# stm32f4stamp-20131027.net
KiCad netlist of a schematic drawn in EAGLE
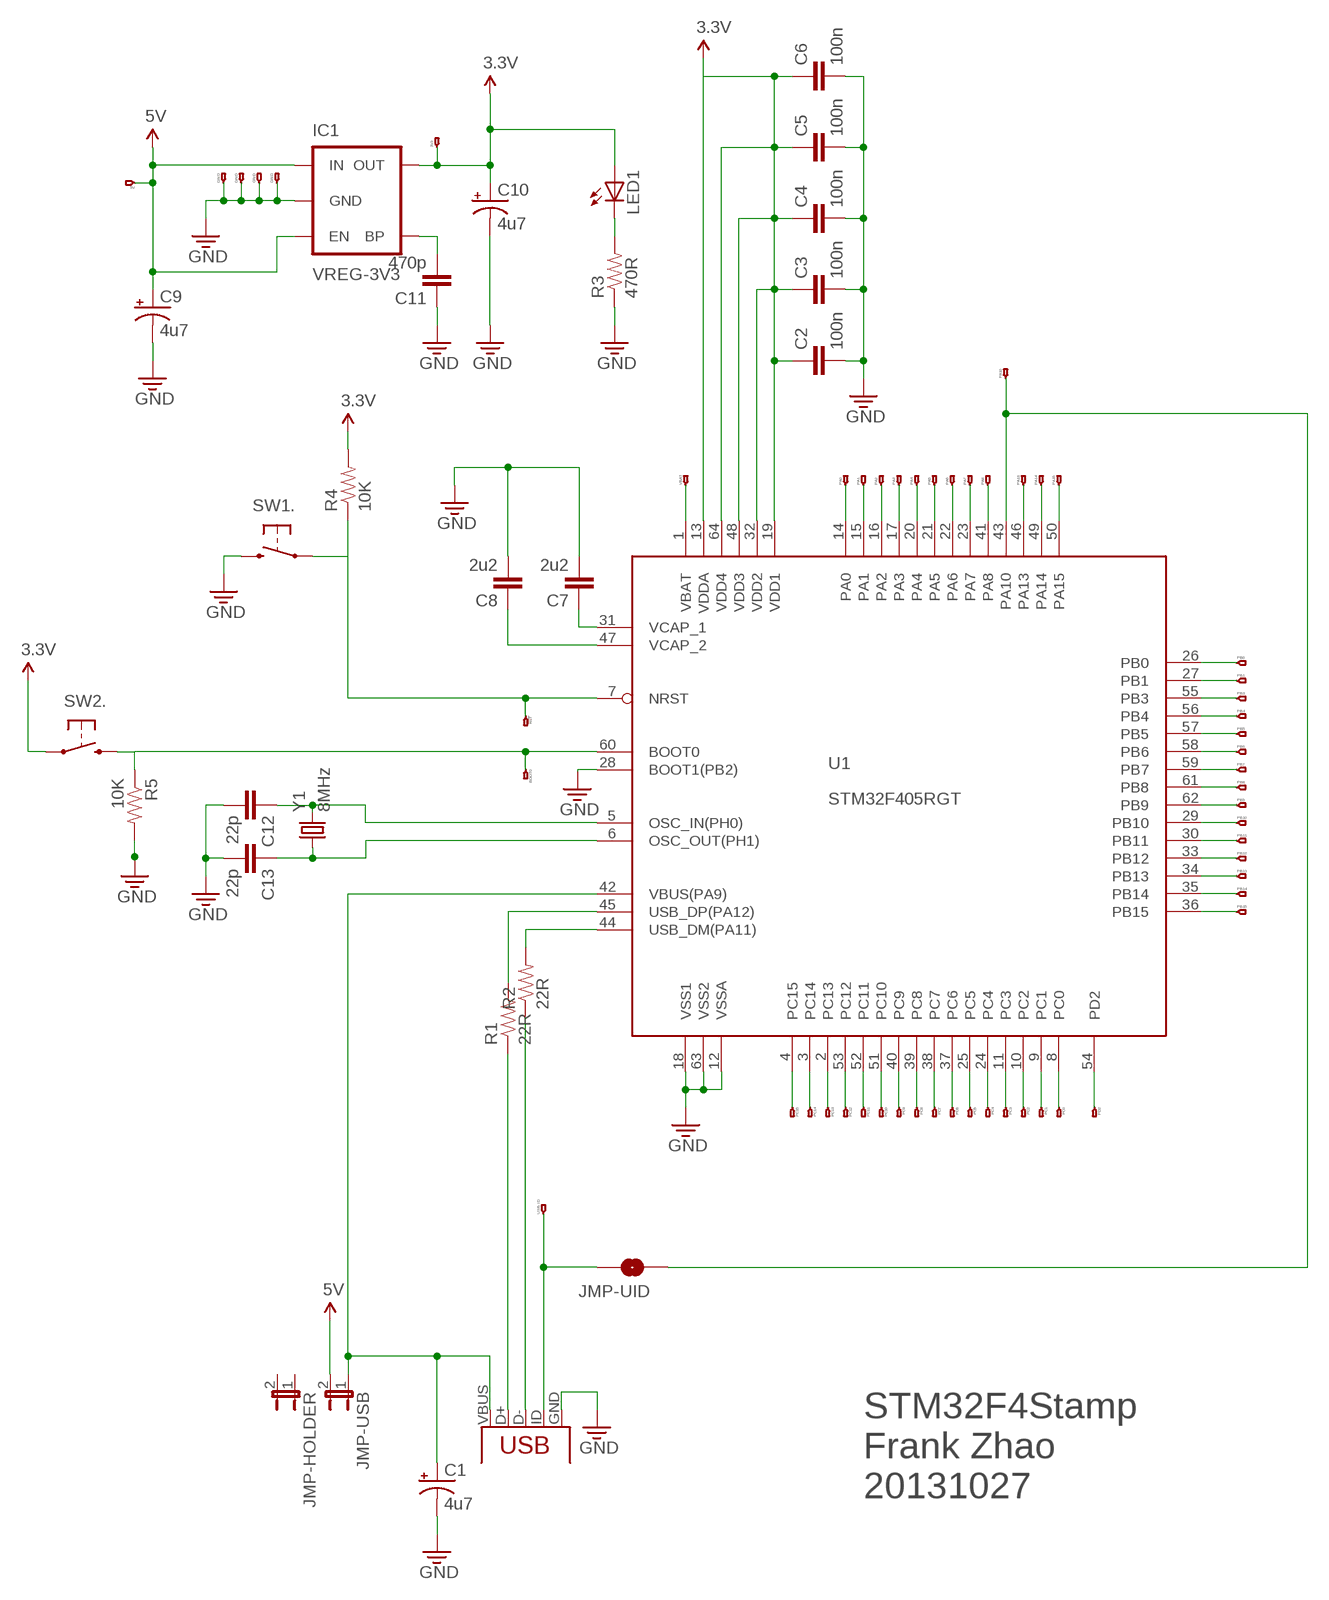
[diagram p0: schematic, sheet 1]

(export (version "E")
  (design (tool "Eeschema 10.0.6"))
  (components
    (comp (ref "C1")
      (value "4u7")
      (footprint "eagle-import:EIA3216-KIT")
      (libsource (lib "eagle-import") (part "CAP_POL1206-KIT"))
    )
    (comp (ref "C2")
      (value "100n")
      (footprint "eagle-import:0603-CAP")
      (libsource (lib "eagle-import") (part "CAP0603-CAP"))
    )
    (comp (ref "C3")
      (value "100n")
      (footprint "eagle-import:0603-CAP")
      (libsource (lib "eagle-import") (part "CAP0603-CAP"))
    )
    (comp (ref "C4")
      (value "100n")
      (footprint "eagle-import:0603-CAP")
      (libsource (lib "eagle-import") (part "CAP0603-CAP"))
    )
    (comp (ref "C5")
      (value "100n")
      (footprint "eagle-import:0603-CAP")
      (libsource (lib "eagle-import") (part "CAP0603-CAP"))
    )
    (comp (ref "C6")
      (value "100n")
      (footprint "eagle-import:0603-CAP")
      (libsource (lib "eagle-import") (part "CAP0603-CAP"))
    )
    (comp (ref "C7")
      (value "2u2")
      (footprint "eagle-import:0603-CAP")
      (libsource (lib "eagle-import") (part "CAP0603-CAP"))
    )
    (comp (ref "C8")
      (value "2u2")
      (footprint "eagle-import:0603-CAP")
      (libsource (lib "eagle-import") (part "CAP0603-CAP"))
    )
    (comp (ref "C9")
      (value "4u7")
      (footprint "eagle-import:EIA3216-KIT")
      (libsource (lib "eagle-import") (part "CAP_POL1206-KIT"))
    )
    (comp (ref "C10")
      (value "4u7")
      (footprint "eagle-import:EIA3216-KIT")
      (libsource (lib "eagle-import") (part "CAP_POL1206-KIT"))
    )
    (comp (ref "C11")
      (value "470p")
      (footprint "eagle-import:0603-CAP")
      (libsource (lib "eagle-import") (part "CAP0603-CAP"))
    )
    (comp (ref "C12")
      (value "22p")
      (footprint "eagle-import:0603-CAP")
      (libsource (lib "eagle-import") (part "CAP0603-CAP"))
    )
    (comp (ref "C13")
      (value "22p")
      (footprint "eagle-import:0603-CAP")
      (libsource (lib "eagle-import") (part "CAP0603-CAP"))
    )
    (comp (ref "IC1")
      (value "VREG-3V3")
      (footprint "eagle-import:SOT23-5")
      (libsource (lib "eagle-import") (part "V_REG_LDOSMD"))
    )
    (comp (ref "JMP-HOLDER")
      (value "JUMPER-2-PTH-2MM")
      (footprint "eagle-import:1X02_2MM_TH")
      (libsource (lib "eagle-import") (part "JUMPER-2-PTH-2MM"))
    )
    (comp (ref "JMP-UID")
      (value "SOLDERJUMPERNC")
      (footprint "eagle-import:SJ_2S")
      (libsource (lib "eagle-import") (part "SOLDERJUMPERNC"))
    )
    (comp (ref "JMP-USB")
      (value "JUMPER-2-PTH-2MM")
      (footprint "eagle-import:1X02_2MM_TH")
      (libsource (lib "eagle-import") (part "JUMPER-2-PTH-2MM"))
    )
    (comp (ref "JP2")
      (value "5V")
      (footprint "eagle-import:1X1-HEADER-HOLE")
      (libsource (lib "eagle-import") (part "HEADERHOLE-HEADERHOLE"))
    )
    (comp (ref "JP3")
      (value "GND")
      (footprint "eagle-import:1X1-HEADER-HOLE")
      (libsource (lib "eagle-import") (part "HEADERHOLE-HEADERHOLE"))
    )
    (comp (ref "JP4")
      (value "3V3")
      (footprint "eagle-import:1X1-HEADER-HOLE")
      (libsource (lib "eagle-import") (part "HEADERHOLE-HEADERHOLE"))
    )
    (comp (ref "JP5")
      (value "GND")
      (footprint "eagle-import:1X1-HEADER-HOLE")
      (libsource (lib "eagle-import") (part "HEADERHOLE-HEADERHOLE"))
    )
    (comp (ref "JP6")
      (value "GND")
      (footprint "eagle-import:1X1-HEADER-HOLE")
      (libsource (lib "eagle-import") (part "HEADERHOLE-HEADERHOLE"))
    )
    (comp (ref "JP7")
      (value "GND")
      (footprint "eagle-import:1X1-HEADER-HOLE")
      (libsource (lib "eagle-import") (part "HEADERHOLE-HEADERHOLE"))
    )
    (comp (ref "JP8")
      (value "PB8")
      (footprint "eagle-import:1X1-HEADER-HOLE")
      (libsource (lib "eagle-import") (part "HEADERHOLE-HEADERHOLE"))
    )
    (comp (ref "JP9")
      (value "PA10")
      (footprint "eagle-import:1X1-HEADER-HOLE")
      (libsource (lib "eagle-import") (part "HEADERHOLE-HEADERHOLE"))
    )
    (comp (ref "JP10")
      (value "PA8")
      (footprint "eagle-import:1X1-HEADER-HOLE")
      (libsource (lib "eagle-import") (part "HEADERHOLE-HEADERHOLE"))
    )
    (comp (ref "JP11")
      (value "PA13")
      (footprint "eagle-import:1X1-HEADER-HOLE")
      (libsource (lib "eagle-import") (part "HEADERHOLE-HEADERHOLE"))
    )
    (comp (ref "JP12")
      (value "PC9")
      (footprint "eagle-import:1X1-HEADER-HOLE")
      (libsource (lib "eagle-import") (part "HEADERHOLE-HEADERHOLE"))
    )
    (comp (ref "JP13")
      (value "PC15")
      (footprint "eagle-import:1X1-HEADER-HOLE")
      (libsource (lib "eagle-import") (part "HEADERHOLE-HEADERHOLE"))
    )
    (comp (ref "JP14")
      (value "PC14")
      (footprint "eagle-import:1X1-HEADER-HOLE")
      (libsource (lib "eagle-import") (part "HEADERHOLE-HEADERHOLE"))
    )
    (comp (ref "JP15")
      (value "PC13")
      (footprint "eagle-import:1X1-HEADER-HOLE")
      (libsource (lib "eagle-import") (part "HEADERHOLE-HEADERHOLE"))
    )
    (comp (ref "JP16")
      (value "PC12")
      (footprint "eagle-import:1X1-HEADER-HOLE")
      (libsource (lib "eagle-import") (part "HEADERHOLE-HEADERHOLE"))
    )
    (comp (ref "JP17")
      (value "PC11")
      (footprint "eagle-import:1X1-HEADER-HOLE")
      (libsource (lib "eagle-import") (part "HEADERHOLE-HEADERHOLE"))
    )
    (comp (ref "JP18")
      (value "PC10")
      (footprint "eagle-import:1X1-HEADER-HOLE")
      (libsource (lib "eagle-import") (part "HEADERHOLE-HEADERHOLE"))
    )
    (comp (ref "JP19")
      (value "PC8")
      (footprint "eagle-import:1X1-HEADER-HOLE")
      (libsource (lib "eagle-import") (part "HEADERHOLE-HEADERHOLE"))
    )
    (comp (ref "JP20")
      (value "PC7")
      (footprint "eagle-import:1X1-HEADER-HOLE")
      (libsource (lib "eagle-import") (part "HEADERHOLE-HEADERHOLE"))
    )
    (comp (ref "JP21")
      (value "PC6")
      (footprint "eagle-import:1X1-HEADER-HOLE")
      (libsource (lib "eagle-import") (part "HEADERHOLE-HEADERHOLE"))
    )
    (comp (ref "JP22")
      (value "PC5")
      (footprint "eagle-import:1X1-HEADER-HOLE")
      (libsource (lib "eagle-import") (part "HEADERHOLE-HEADERHOLE"))
    )
    (comp (ref "JP23")
      (value "PC4")
      (footprint "eagle-import:1X1-HEADER-HOLE")
      (libsource (lib "eagle-import") (part "HEADERHOLE-HEADERHOLE"))
    )
    (comp (ref "JP24")
      (value "PC3")
      (footprint "eagle-import:1X1-HEADER-HOLE")
      (libsource (lib "eagle-import") (part "HEADERHOLE-HEADERHOLE"))
    )
    (comp (ref "JP25")
      (value "PC2")
      (footprint "eagle-import:1X1-HEADER-HOLE")
      (libsource (lib "eagle-import") (part "HEADERHOLE-HEADERHOLE"))
    )
    (comp (ref "JP26")
      (value "PC1")
      (footprint "eagle-import:1X1-HEADER-HOLE")
      (libsource (lib "eagle-import") (part "HEADERHOLE-HEADERHOLE"))
    )
    (comp (ref "JP27")
      (value "PC0")
      (footprint "eagle-import:1X1-HEADER-HOLE")
      (libsource (lib "eagle-import") (part "HEADERHOLE-HEADERHOLE"))
    )
    (comp (ref "JP28")
      (value "PD2")
      (footprint "eagle-import:1X1-HEADER-HOLE")
      (libsource (lib "eagle-import") (part "HEADERHOLE-HEADERHOLE"))
    )
    (comp (ref "JP29")
      (value "PA0")
      (footprint "eagle-import:1X1-HEADER-HOLE")
      (libsource (lib "eagle-import") (part "HEADERHOLE-HEADERHOLE"))
    )
    (comp (ref "JP30")
      (value "PA1")
      (footprint "eagle-import:1X1-HEADER-HOLE")
      (libsource (lib "eagle-import") (part "HEADERHOLE-HEADERHOLE"))
    )
    (comp (ref "JP31")
      (value "PA2")
      (footprint "eagle-import:1X1-HEADER-HOLE")
      (libsource (lib "eagle-import") (part "HEADERHOLE-HEADERHOLE"))
    )
    (comp (ref "JP32")
      (value "PA3")
      (footprint "eagle-import:1X1-HEADER-HOLE")
      (libsource (lib "eagle-import") (part "HEADERHOLE-HEADERHOLE"))
    )
    (comp (ref "JP33")
      (value "PA4")
      (footprint "eagle-import:1X1-HEADER-HOLE")
      (libsource (lib "eagle-import") (part "HEADERHOLE-HEADERHOLE"))
    )
    (comp (ref "JP34")
      (value "PA5")
      (footprint "eagle-import:1X1-HEADER-HOLE")
      (libsource (lib "eagle-import") (part "HEADERHOLE-HEADERHOLE"))
    )
    (comp (ref "JP35")
      (value "PA6")
      (footprint "eagle-import:1X1-HEADER-HOLE")
      (libsource (lib "eagle-import") (part "HEADERHOLE-HEADERHOLE"))
    )
    (comp (ref "JP36")
      (value "PA7")
      (footprint "eagle-import:1X1-HEADER-HOLE")
      (libsource (lib "eagle-import") (part "HEADERHOLE-HEADERHOLE"))
    )
    (comp (ref "JP37")
      (value "PA14")
      (footprint "eagle-import:1X1-HEADER-HOLE")
      (libsource (lib "eagle-import") (part "HEADERHOLE-HEADERHOLE"))
    )
    (comp (ref "JP38")
      (value "PA15")
      (footprint "eagle-import:1X1-HEADER-HOLE")
      (libsource (lib "eagle-import") (part "HEADERHOLE-HEADERHOLE"))
    )
    (comp (ref "JP39")
      (value "PB0")
      (footprint "eagle-import:1X1-HEADER-HOLE")
      (libsource (lib "eagle-import") (part "HEADERHOLE-HEADERHOLE"))
    )
    (comp (ref "JP40")
      (value "PB1")
      (footprint "eagle-import:1X1-HEADER-HOLE")
      (libsource (lib "eagle-import") (part "HEADERHOLE-HEADERHOLE"))
    )
    (comp (ref "JP41")
      (value "PB3")
      (footprint "eagle-import:1X1-HEADER-HOLE")
      (libsource (lib "eagle-import") (part "HEADERHOLE-HEADERHOLE"))
    )
    (comp (ref "JP42")
      (value "PB4")
      (footprint "eagle-import:1X1-HEADER-HOLE")
      (libsource (lib "eagle-import") (part "HEADERHOLE-HEADERHOLE"))
    )
    (comp (ref "JP43")
      (value "PB5")
      (footprint "eagle-import:1X1-HEADER-HOLE")
      (libsource (lib "eagle-import") (part "HEADERHOLE-HEADERHOLE"))
    )
    (comp (ref "JP44")
      (value "PB6")
      (footprint "eagle-import:1X1-HEADER-HOLE")
      (libsource (lib "eagle-import") (part "HEADERHOLE-HEADERHOLE"))
    )
    (comp (ref "JP45")
      (value "PB7")
      (footprint "eagle-import:1X1-HEADER-HOLE")
      (libsource (lib "eagle-import") (part "HEADERHOLE-HEADERHOLE"))
    )
    (comp (ref "JP46")
      (value "PB9")
      (footprint "eagle-import:1X1-HEADER-HOLE")
      (libsource (lib "eagle-import") (part "HEADERHOLE-HEADERHOLE"))
    )
    (comp (ref "JP47")
      (value "PB10")
      (footprint "eagle-import:1X1-HEADER-HOLE")
      (libsource (lib "eagle-import") (part "HEADERHOLE-HEADERHOLE"))
    )
    (comp (ref "JP48")
      (value "PB11")
      (footprint "eagle-import:1X1-HEADER-HOLE")
      (libsource (lib "eagle-import") (part "HEADERHOLE-HEADERHOLE"))
    )
    (comp (ref "JP49")
      (value "PB12")
      (footprint "eagle-import:1X1-HEADER-HOLE")
      (libsource (lib "eagle-import") (part "HEADERHOLE-HEADERHOLE"))
    )
    (comp (ref "JP50")
      (value "PB13")
      (footprint "eagle-import:1X1-HEADER-HOLE")
      (libsource (lib "eagle-import") (part "HEADERHOLE-HEADERHOLE"))
    )
    (comp (ref "JP51")
      (value "PB14")
      (footprint "eagle-import:1X1-HEADER-HOLE")
      (libsource (lib "eagle-import") (part "HEADERHOLE-HEADERHOLE"))
    )
    (comp (ref "JP52")
      (value "PB15")
      (footprint "eagle-import:1X1-HEADER-HOLE")
      (libsource (lib "eagle-import") (part "HEADERHOLE-HEADERHOLE"))
    )
    (comp (ref "JP53")
      (value "VBAT")
      (footprint "eagle-import:1X1-HEADER-HOLE")
      (libsource (lib "eagle-import") (part "HEADERHOLE-HEADERHOLE"))
    )
    (comp (ref "JP54")
      (value "!RST")
      (footprint "eagle-import:1X1-HEADER-HOLE")
      (libsource (lib "eagle-import") (part "HEADERHOLE-HEADERHOLE"))
    )
    (comp (ref "JP55")
      (value "BOOT0")
      (footprint "eagle-import:1X1-HEADER-HOLE")
      (libsource (lib "eagle-import") (part "HEADERHOLE-HEADERHOLE"))
    )
    (comp (ref "JP56")
      (value "USB-ID")
      (footprint "eagle-import:1X1-HEADER-HOLE")
      (libsource (lib "eagle-import") (part "HEADERHOLE-HEADERHOLE"))
    )
    (comp (ref "LED1")
      (value "LED0603")
      (footprint "eagle-import:LED-0603")
      (libsource (lib "eagle-import") (part "LED0603"))
    )
    (comp (ref "R1")
      (value "22R")
      (footprint "eagle-import:0603-RES")
      (libsource (lib "eagle-import") (part "RESISTOR0603-RES"))
    )
    (comp (ref "R2")
      (value "22R")
      (footprint "eagle-import:0603-RES")
      (libsource (lib "eagle-import") (part "RESISTOR0603-RES"))
    )
    (comp (ref "R3")
      (value "470R")
      (footprint "eagle-import:0603-RES")
      (libsource (lib "eagle-import") (part "RESISTOR0603-RES"))
    )
    (comp (ref "R4")
      (value "10K")
      (footprint "eagle-import:0603-RES")
      (libsource (lib "eagle-import") (part "RESISTOR0603-RES"))
    )
    (comp (ref "R5")
      (value "10K")
      (footprint "eagle-import:0603-RES")
      (libsource (lib "eagle-import") (part "RESISTOR0603-RES"))
    )
    (comp (ref "SW1")
      (value "!RST")
      (footprint "eagle-import:SWITCH-TACT-B3U-1100P-B")
      (libsource (lib "eagle-import") (part "SWITCH-B3U-1110-BOSS"))
    )
    (comp (ref "SW2")
      (value "BOOT")
      (footprint "eagle-import:SWITCH-TACT-B3U-1100P-B")
      (libsource (lib "eagle-import") (part "SWITCH-B3U-1110-BOSS"))
    )
    (comp (ref "U1")
      (value "STM32F405RGT")
      (footprint "eagle-import:LQFP64")
      (libsource (lib "eagle-import") (part "STM32F405RGT"))
    )
    (comp (ref "USB")
      (value "USB-MICROB-SMD")
      (footprint "eagle-import:USB-MICROB-SMD")
      (libsource (lib "eagle-import") (part "USB-MICROB-SMD"))
    )
    (comp (ref "Y1")
      (value "8MHz")
      (footprint "eagle-import:CRYSTAL-SMD-5X3")
      (libsource (lib "eagle-import") (part "CRYSTAL5X3"))
    )
  )
  (nets
    (net (code "1") (name "3.3V") (class "Default")
      (node (ref "C10") (pin "A") (pinfunction "+_A") (pintype "passive"))
      (node (ref "C2") (pin "1") (pinfunction "1_1") (pintype "passive"))
      (node (ref "C3") (pin "1") (pinfunction "1_1") (pintype "passive"))
      (node (ref "C4") (pin "1") (pinfunction "1_1") (pintype "passive"))
      (node (ref "C5") (pin "1") (pinfunction "1_1") (pintype "passive"))
      (node (ref "C6") (pin "1") (pinfunction "1_1") (pintype "passive"))
      (node (ref "IC1") (pin "5") (pinfunction "OUT_5") (pintype "passive"))
      (node (ref "JP4") (pin "1") (pinfunction "P$1_1") (pintype "bidirectional"))
      (node (ref "LED1") (pin "A") (pinfunction "A_A") (pintype "passive"))
      (node (ref "R4") (pin "2") (pinfunction "2_2") (pintype "passive"))
      (node (ref "SW2") (pin "1") (pinfunction "1_1") (pintype "passive"))
      (node (ref "U1") (pin "13") (pinfunction "VDDA_13") (pintype "power_in"))
      (node (ref "U1") (pin "19") (pinfunction "VDD1_19") (pintype "power_in"))
      (node (ref "U1") (pin "32") (pinfunction "VDD2_32") (pintype "power_in"))
      (node (ref "U1") (pin "48") (pinfunction "VDD3_48") (pintype "power_in"))
      (node (ref "U1") (pin "64") (pinfunction "VDD4_64") (pintype "power_in"))
    )
    (net (code "2") (name "5V") (class "Default")
      (node (ref "C9") (pin "A") (pinfunction "+_A") (pintype "passive"))
      (node (ref "IC1") (pin "1") (pinfunction "IN_1") (pintype "input"))
      (node (ref "IC1") (pin "3") (pinfunction "EN_3") (pintype "input"))
      (node (ref "JMP-USB") (pin "2") (pinfunction "2_2") (pintype "passive"))
      (node (ref "JP2") (pin "1") (pinfunction "P$1_1") (pintype "bidirectional"))
    )
    (net (code "3") (name "GND") (class "Default")
      (node (ref "C1") (pin "C") (pinfunction "-_C") (pintype "passive"))
      (node (ref "C10") (pin "C") (pinfunction "-_C") (pintype "passive"))
      (node (ref "C11") (pin "1") (pinfunction "1_1") (pintype "passive"))
      (node (ref "C12") (pin "2") (pinfunction "2_2") (pintype "passive"))
      (node (ref "C13") (pin "2") (pinfunction "2_2") (pintype "passive"))
      (node (ref "C2") (pin "2") (pinfunction "2_2") (pintype "passive"))
      (node (ref "C3") (pin "2") (pinfunction "2_2") (pintype "passive"))
      (node (ref "C4") (pin "2") (pinfunction "2_2") (pintype "passive"))
      (node (ref "C5") (pin "2") (pinfunction "2_2") (pintype "passive"))
      (node (ref "C6") (pin "2") (pinfunction "2_2") (pintype "passive"))
      (node (ref "C7") (pin "2") (pinfunction "2_2") (pintype "passive"))
      (node (ref "C8") (pin "2") (pinfunction "2_2") (pintype "passive"))
      (node (ref "C9") (pin "C") (pinfunction "-_C") (pintype "passive"))
      (node (ref "IC1") (pin "2") (pinfunction "GND_2") (pintype "input"))
      (node (ref "JP3") (pin "1") (pinfunction "P$1_1") (pintype "bidirectional"))
      (node (ref "JP5") (pin "1") (pinfunction "P$1_1") (pintype "bidirectional"))
      (node (ref "JP6") (pin "1") (pinfunction "P$1_1") (pintype "bidirectional"))
      (node (ref "JP7") (pin "1") (pinfunction "P$1_1") (pintype "bidirectional"))
      (node (ref "R3") (pin "1") (pinfunction "1_1") (pintype "passive"))
      (node (ref "R5") (pin "2") (pinfunction "2_2") (pintype "passive"))
      (node (ref "SW1") (pin "2") (pinfunction "2_2") (pintype "passive"))
      (node (ref "SW1") (pin "BOSS") (pinfunction "P$1_BOSS") (pintype "bidirectional"))
      (node (ref "SW2") (pin "BOSS") (pinfunction "P$1_BOSS") (pintype "bidirectional"))
      (node (ref "U1") (pin "12") (pinfunction "VSSA_12") (pintype "power_in"))
      (node (ref "U1") (pin "18") (pinfunction "VSS1_18") (pintype "power_in"))
      (node (ref "U1") (pin "28") (pinfunction "BOOT1(PB2)_28") (pintype "input"))
      (node (ref "U1") (pin "63") (pinfunction "VSS2_63") (pintype "power_in"))
      (node (ref "USB") (pin "GND") (pinfunction "GND_GND") (pintype "bidirectional"))
      (node (ref "USB") (pin "MT1") (pinfunction "P$1_MT1") (pintype "bidirectional"))
      (node (ref "USB") (pin "MT2") (pinfunction "P$1_MT2") (pintype "bidirectional"))
      (node (ref "USB") (pin "MT3") (pinfunction "P$1_MT3") (pintype "bidirectional"))
      (node (ref "USB") (pin "MT4") (pinfunction "P$1_MT4") (pintype "bidirectional"))
    )
    (net (code "4") (name "Net-(C1-+)") (class "Default")
      (node (ref "C1") (pin "A") (pinfunction "+_A") (pintype "passive"))
      (node (ref "JMP-USB") (pin "1") (pinfunction "1_1") (pintype "passive"))
      (node (ref "U1") (pin "42") (pinfunction "VBUS(PA9)_42") (pintype "bidirectional"))
      (node (ref "USB") (pin "VBUS") (pinfunction "VBUS_VBUS") (pintype "bidirectional"))
    )
    (net (code "5") (name "Net-(IC1-BP)") (class "Default")
      (node (ref "C11") (pin "2") (pinfunction "2_2") (pintype "passive"))
      (node (ref "IC1") (pin "4") (pinfunction "BP_4") (pintype "input"))
    )
    (net (code "6") (name "Net-(JP8-P$1)") (class "Default")
      (node (ref "JP8") (pin "1") (pinfunction "P$1_1") (pintype "bidirectional"))
      (node (ref "U1") (pin "61") (pinfunction "PB8_61") (pintype "bidirectional"))
    )
    (net (code "7") (name "Net-(JP9-P$1)") (class "Default")
      (node (ref "JMP-UID") (pin "1") (pinfunction "1_1") (pintype "passive"))
      (node (ref "JP9") (pin "1") (pinfunction "P$1_1") (pintype "bidirectional"))
      (node (ref "U1") (pin "43") (pinfunction "PA10_43") (pintype "bidirectional"))
    )
    (net (code "8") (name "Net-(JP10-P$1)") (class "Default")
      (node (ref "JP10") (pin "1") (pinfunction "P$1_1") (pintype "bidirectional"))
      (node (ref "U1") (pin "41") (pinfunction "PA8_41") (pintype "bidirectional"))
    )
    (net (code "9") (name "Net-(JP11-P$1)") (class "Default")
      (node (ref "JP11") (pin "1") (pinfunction "P$1_1") (pintype "bidirectional"))
      (node (ref "U1") (pin "46") (pinfunction "PA13_46") (pintype "bidirectional"))
    )
    (net (code "10") (name "Net-(JP12-P$1)") (class "Default")
      (node (ref "JP12") (pin "1") (pinfunction "P$1_1") (pintype "bidirectional"))
      (node (ref "U1") (pin "40") (pinfunction "PC9_40") (pintype "bidirectional"))
    )
    (net (code "11") (name "Net-(JP13-P$1)") (class "Default")
      (node (ref "JP13") (pin "1") (pinfunction "P$1_1") (pintype "bidirectional"))
      (node (ref "U1") (pin "4") (pinfunction "PC15_4") (pintype "bidirectional"))
    )
    (net (code "12") (name "Net-(JP14-P$1)") (class "Default")
      (node (ref "JP14") (pin "1") (pinfunction "P$1_1") (pintype "bidirectional"))
      (node (ref "U1") (pin "3") (pinfunction "PC14_3") (pintype "bidirectional"))
    )
    (net (code "13") (name "Net-(JP15-P$1)") (class "Default")
      (node (ref "JP15") (pin "1") (pinfunction "P$1_1") (pintype "bidirectional"))
      (node (ref "U1") (pin "2") (pinfunction "PC13_2") (pintype "bidirectional"))
    )
    (net (code "14") (name "Net-(JP16-P$1)") (class "Default")
      (node (ref "JP16") (pin "1") (pinfunction "P$1_1") (pintype "bidirectional"))
      (node (ref "U1") (pin "53") (pinfunction "PC12_53") (pintype "bidirectional"))
    )
    (net (code "15") (name "Net-(JP17-P$1)") (class "Default")
      (node (ref "JP17") (pin "1") (pinfunction "P$1_1") (pintype "bidirectional"))
      (node (ref "U1") (pin "52") (pinfunction "PC11_52") (pintype "bidirectional"))
    )
    (net (code "16") (name "Net-(JP18-P$1)") (class "Default")
      (node (ref "JP18") (pin "1") (pinfunction "P$1_1") (pintype "bidirectional"))
      (node (ref "U1") (pin "51") (pinfunction "PC10_51") (pintype "bidirectional"))
    )
    (net (code "17") (name "Net-(JP19-P$1)") (class "Default")
      (node (ref "JP19") (pin "1") (pinfunction "P$1_1") (pintype "bidirectional"))
      (node (ref "U1") (pin "39") (pinfunction "PC8_39") (pintype "bidirectional"))
    )
    (net (code "18") (name "Net-(JP20-P$1)") (class "Default")
      (node (ref "JP20") (pin "1") (pinfunction "P$1_1") (pintype "bidirectional"))
      (node (ref "U1") (pin "38") (pinfunction "PC7_38") (pintype "bidirectional"))
    )
    (net (code "19") (name "Net-(JP21-P$1)") (class "Default")
      (node (ref "JP21") (pin "1") (pinfunction "P$1_1") (pintype "bidirectional"))
      (node (ref "U1") (pin "37") (pinfunction "PC6_37") (pintype "bidirectional"))
    )
    (net (code "20") (name "Net-(JP22-P$1)") (class "Default")
      (node (ref "JP22") (pin "1") (pinfunction "P$1_1") (pintype "bidirectional"))
      (node (ref "U1") (pin "25") (pinfunction "PC5_25") (pintype "bidirectional"))
    )
    (net (code "21") (name "Net-(JP23-P$1)") (class "Default")
      (node (ref "JP23") (pin "1") (pinfunction "P$1_1") (pintype "bidirectional"))
      (node (ref "U1") (pin "24") (pinfunction "PC4_24") (pintype "bidirectional"))
    )
    (net (code "22") (name "Net-(JP24-P$1)") (class "Default")
      (node (ref "JP24") (pin "1") (pinfunction "P$1_1") (pintype "bidirectional"))
      (node (ref "U1") (pin "11") (pinfunction "PC3_11") (pintype "bidirectional"))
    )
    (net (code "23") (name "Net-(JP25-P$1)") (class "Default")
      (node (ref "JP25") (pin "1") (pinfunction "P$1_1") (pintype "bidirectional"))
      (node (ref "U1") (pin "10") (pinfunction "PC2_10") (pintype "bidirectional"))
    )
    (net (code "24") (name "Net-(JP26-P$1)") (class "Default")
      (node (ref "JP26") (pin "1") (pinfunction "P$1_1") (pintype "bidirectional"))
      (node (ref "U1") (pin "9") (pinfunction "PC1_9") (pintype "bidirectional"))
    )
    (net (code "25") (name "Net-(JP27-P$1)") (class "Default")
      (node (ref "JP27") (pin "1") (pinfunction "P$1_1") (pintype "bidirectional"))
      (node (ref "U1") (pin "8") (pinfunction "PC0_8") (pintype "bidirectional"))
    )
    (net (code "26") (name "Net-(JP28-P$1)") (class "Default")
      (node (ref "JP28") (pin "1") (pinfunction "P$1_1") (pintype "bidirectional"))
      (node (ref "U1") (pin "54") (pinfunction "PD2_54") (pintype "bidirectional"))
    )
    (net (code "27") (name "Net-(JP29-P$1)") (class "Default")
      (node (ref "JP29") (pin "1") (pinfunction "P$1_1") (pintype "bidirectional"))
      (node (ref "U1") (pin "14") (pinfunction "PA0_14") (pintype "bidirectional"))
    )
    (net (code "28") (name "Net-(JP30-P$1)") (class "Default")
      (node (ref "JP30") (pin "1") (pinfunction "P$1_1") (pintype "bidirectional"))
      (node (ref "U1") (pin "15") (pinfunction "PA1_15") (pintype "bidirectional"))
    )
    (net (code "29") (name "Net-(JP31-P$1)") (class "Default")
      (node (ref "JP31") (pin "1") (pinfunction "P$1_1") (pintype "bidirectional"))
      (node (ref "U1") (pin "16") (pinfunction "PA2_16") (pintype "bidirectional"))
    )
    (net (code "30") (name "Net-(JP32-P$1)") (class "Default")
      (node (ref "JP32") (pin "1") (pinfunction "P$1_1") (pintype "bidirectional"))
      (node (ref "U1") (pin "17") (pinfunction "PA3_17") (pintype "bidirectional"))
    )
    (net (code "31") (name "Net-(JP33-P$1)") (class "Default")
      (node (ref "JP33") (pin "1") (pinfunction "P$1_1") (pintype "bidirectional"))
      (node (ref "U1") (pin "20") (pinfunction "PA4_20") (pintype "bidirectional"))
    )
    (net (code "32") (name "Net-(JP34-P$1)") (class "Default")
      (node (ref "JP34") (pin "1") (pinfunction "P$1_1") (pintype "bidirectional"))
      (node (ref "U1") (pin "21") (pinfunction "PA5_21") (pintype "bidirectional"))
    )
    (net (code "33") (name "Net-(JP35-P$1)") (class "Default")
      (node (ref "JP35") (pin "1") (pinfunction "P$1_1") (pintype "bidirectional"))
      (node (ref "U1") (pin "22") (pinfunction "PA6_22") (pintype "bidirectional"))
    )
    (net (code "34") (name "Net-(JP36-P$1)") (class "Default")
      (node (ref "JP36") (pin "1") (pinfunction "P$1_1") (pintype "bidirectional"))
      (node (ref "U1") (pin "23") (pinfunction "PA7_23") (pintype "bidirectional"))
    )
    (net (code "35") (name "Net-(JP37-P$1)") (class "Default")
      (node (ref "JP37") (pin "1") (pinfunction "P$1_1") (pintype "bidirectional"))
      (node (ref "U1") (pin "49") (pinfunction "PA14_49") (pintype "bidirectional"))
    )
    (net (code "36") (name "Net-(JP38-P$1)") (class "Default")
      (node (ref "JP38") (pin "1") (pinfunction "P$1_1") (pintype "bidirectional"))
      (node (ref "U1") (pin "50") (pinfunction "PA15_50") (pintype "bidirectional"))
    )
    (net (code "37") (name "Net-(JP39-P$1)") (class "Default")
      (node (ref "JP39") (pin "1") (pinfunction "P$1_1") (pintype "bidirectional"))
      (node (ref "U1") (pin "26") (pinfunction "PB0_26") (pintype "bidirectional"))
    )
    (net (code "38") (name "Net-(JP40-P$1)") (class "Default")
      (node (ref "JP40") (pin "1") (pinfunction "P$1_1") (pintype "bidirectional"))
      (node (ref "U1") (pin "27") (pinfunction "PB1_27") (pintype "bidirectional"))
    )
    (net (code "39") (name "Net-(JP41-P$1)") (class "Default")
      (node (ref "JP41") (pin "1") (pinfunction "P$1_1") (pintype "bidirectional"))
      (node (ref "U1") (pin "55") (pinfunction "PB3_55") (pintype "bidirectional"))
    )
    (net (code "40") (name "Net-(JP42-P$1)") (class "Default")
      (node (ref "JP42") (pin "1") (pinfunction "P$1_1") (pintype "bidirectional"))
      (node (ref "U1") (pin "56") (pinfunction "PB4_56") (pintype "bidirectional"))
    )
    (net (code "41") (name "Net-(JP43-P$1)") (class "Default")
      (node (ref "JP43") (pin "1") (pinfunction "P$1_1") (pintype "bidirectional"))
      (node (ref "U1") (pin "57") (pinfunction "PB5_57") (pintype "bidirectional"))
    )
    (net (code "42") (name "Net-(JP44-P$1)") (class "Default")
      (node (ref "JP44") (pin "1") (pinfunction "P$1_1") (pintype "bidirectional"))
      (node (ref "U1") (pin "58") (pinfunction "PB6_58") (pintype "bidirectional"))
    )
    (net (code "43") (name "Net-(JP45-P$1)") (class "Default")
      (node (ref "JP45") (pin "1") (pinfunction "P$1_1") (pintype "bidirectional"))
      (node (ref "U1") (pin "59") (pinfunction "PB7_59") (pintype "bidirectional"))
    )
    (net (code "44") (name "Net-(JP46-P$1)") (class "Default")
      (node (ref "JP46") (pin "1") (pinfunction "P$1_1") (pintype "bidirectional"))
      (node (ref "U1") (pin "62") (pinfunction "PB9_62") (pintype "bidirectional"))
    )
    (net (code "45") (name "Net-(JP47-P$1)") (class "Default")
      (node (ref "JP47") (pin "1") (pinfunction "P$1_1") (pintype "bidirectional"))
      (node (ref "U1") (pin "29") (pinfunction "PB10_29") (pintype "bidirectional"))
    )
    (net (code "46") (name "Net-(JP48-P$1)") (class "Default")
      (node (ref "JP48") (pin "1") (pinfunction "P$1_1") (pintype "bidirectional"))
      (node (ref "U1") (pin "30") (pinfunction "PB11_30") (pintype "bidirectional"))
    )
    (net (code "47") (name "Net-(JP49-P$1)") (class "Default")
      (node (ref "JP49") (pin "1") (pinfunction "P$1_1") (pintype "bidirectional"))
      (node (ref "U1") (pin "33") (pinfunction "PB12_33") (pintype "bidirectional"))
    )
    (net (code "48") (name "Net-(JP50-P$1)") (class "Default")
      (node (ref "JP50") (pin "1") (pinfunction "P$1_1") (pintype "bidirectional"))
      (node (ref "U1") (pin "34") (pinfunction "PB13_34") (pintype "bidirectional"))
    )
    (net (code "49") (name "Net-(JP51-P$1)") (class "Default")
      (node (ref "JP51") (pin "1") (pinfunction "P$1_1") (pintype "bidirectional"))
      (node (ref "U1") (pin "35") (pinfunction "PB14_35") (pintype "bidirectional"))
    )
    (net (code "50") (name "Net-(JP52-P$1)") (class "Default")
      (node (ref "JP52") (pin "1") (pinfunction "P$1_1") (pintype "bidirectional"))
      (node (ref "U1") (pin "36") (pinfunction "PB15_36") (pintype "bidirectional"))
    )
    (net (code "51") (name "Net-(JP53-P$1)") (class "Default")
      (node (ref "JP53") (pin "1") (pinfunction "P$1_1") (pintype "bidirectional"))
      (node (ref "U1") (pin "1") (pinfunction "VBAT_1") (pintype "power_in"))
    )
    (net (code "52") (name "Net-(JP54-P$1)") (class "Default")
      (node (ref "JP54") (pin "1") (pinfunction "P$1_1") (pintype "bidirectional"))
      (node (ref "R4") (pin "1") (pinfunction "1_1") (pintype "passive"))
      (node (ref "SW1") (pin "1") (pinfunction "1_1") (pintype "passive"))
      (node (ref "U1") (pin "7") (pinfunction "NRST_7") (pintype "input"))
    )
    (net (code "53") (name "Net-(JP55-P$1)") (class "Default")
      (node (ref "JP55") (pin "1") (pinfunction "P$1_1") (pintype "bidirectional"))
      (node (ref "R5") (pin "1") (pinfunction "1_1") (pintype "passive"))
      (node (ref "SW2") (pin "2") (pinfunction "2_2") (pintype "passive"))
      (node (ref "U1") (pin "60") (pinfunction "BOOT0_60") (pintype "input"))
    )
    (net (code "54") (name "Net-(JP56-P$1)") (class "Default")
      (node (ref "JMP-UID") (pin "2") (pinfunction "2_2") (pintype "passive"))
      (node (ref "JP56") (pin "1") (pinfunction "P$1_1") (pintype "bidirectional"))
      (node (ref "USB") (pin "ID") (pinfunction "ID_ID") (pintype "bidirectional"))
    )
    (net (code "55") (name "Net-(LED1-PadC)") (class "Default")
      (node (ref "LED1") (pin "C") (pinfunction "C_C") (pintype "passive"))
      (node (ref "R3") (pin "2") (pinfunction "2_2") (pintype "passive"))
    )
    (net (code "56") (name "Net-(R1-Pad1)") (class "Default")
      (node (ref "R1") (pin "1") (pinfunction "1_1") (pintype "passive"))
      (node (ref "USB") (pin "D+") (pinfunction "D+_D+") (pintype "bidirectional"))
    )
    (net (code "57") (name "Net-(R2-Pad1)") (class "Default")
      (node (ref "R2") (pin "1") (pinfunction "1_1") (pintype "passive"))
      (node (ref "USB") (pin "D-") (pinfunction "D-_D-") (pintype "bidirectional"))
    )
    (net (code "58") (name "Net-(U1-OSC_IN(PH0))") (class "Default")
      (node (ref "C12") (pin "1") (pinfunction "1_1") (pintype "passive"))
      (node (ref "U1") (pin "5") (pinfunction "OSC_IN(PH0)_5") (pintype "bidirectional"))
      (node (ref "Y1") (pin "3") (pinfunction "2_3") (pintype "passive"))
    )
    (net (code "59") (name "Net-(U1-OSC_OUT(PH1))") (class "Default")
      (node (ref "C13") (pin "1") (pinfunction "1_1") (pintype "passive"))
      (node (ref "U1") (pin "6") (pinfunction "OSC_OUT(PH1)_6") (pintype "bidirectional"))
      (node (ref "Y1") (pin "1") (pinfunction "1_1") (pintype "passive"))
    )
    (net (code "60") (name "Net-(U1-USB_DM(PA11))") (class "Default")
      (node (ref "R2") (pin "2") (pinfunction "2_2") (pintype "passive"))
      (node (ref "U1") (pin "44") (pinfunction "USB_DM(PA11)_44") (pintype "bidirectional"))
    )
    (net (code "61") (name "Net-(U1-USB_DP(PA12))") (class "Default")
      (node (ref "R1") (pin "2") (pinfunction "2_2") (pintype "passive"))
      (node (ref "U1") (pin "45") (pinfunction "USB_DP(PA12)_45") (pintype "bidirectional"))
    )
    (net (code "62") (name "Net-(U1-VCAP_1)") (class "Default")
      (node (ref "C7") (pin "1") (pinfunction "1_1") (pintype "passive"))
      (node (ref "U1") (pin "31") (pinfunction "VCAP_1_31") (pintype "bidirectional"))
    )
    (net (code "63") (name "Net-(U1-VCAP_2)") (class "Default")
      (node (ref "C8") (pin "1") (pinfunction "1_1") (pintype "passive"))
      (node (ref "U1") (pin "47") (pinfunction "VCAP_2_47") (pintype "bidirectional"))
    )
    (net (code "64") (name "unconnected-(JMP-HOLDER-Pad1)") (class "Default")
      (node (ref "JMP-HOLDER") (pin "1") (pinfunction "1_1") (pintype "passive"))
    )
    (net (code "65") (name "unconnected-(JMP-HOLDER-Pad2)") (class "Default")
      (node (ref "JMP-HOLDER") (pin "2") (pinfunction "2_2") (pintype "passive"))
    )
  )
)
